# Front_LDR.net
KiCad netlist of a schematic drawn in Altium Designer
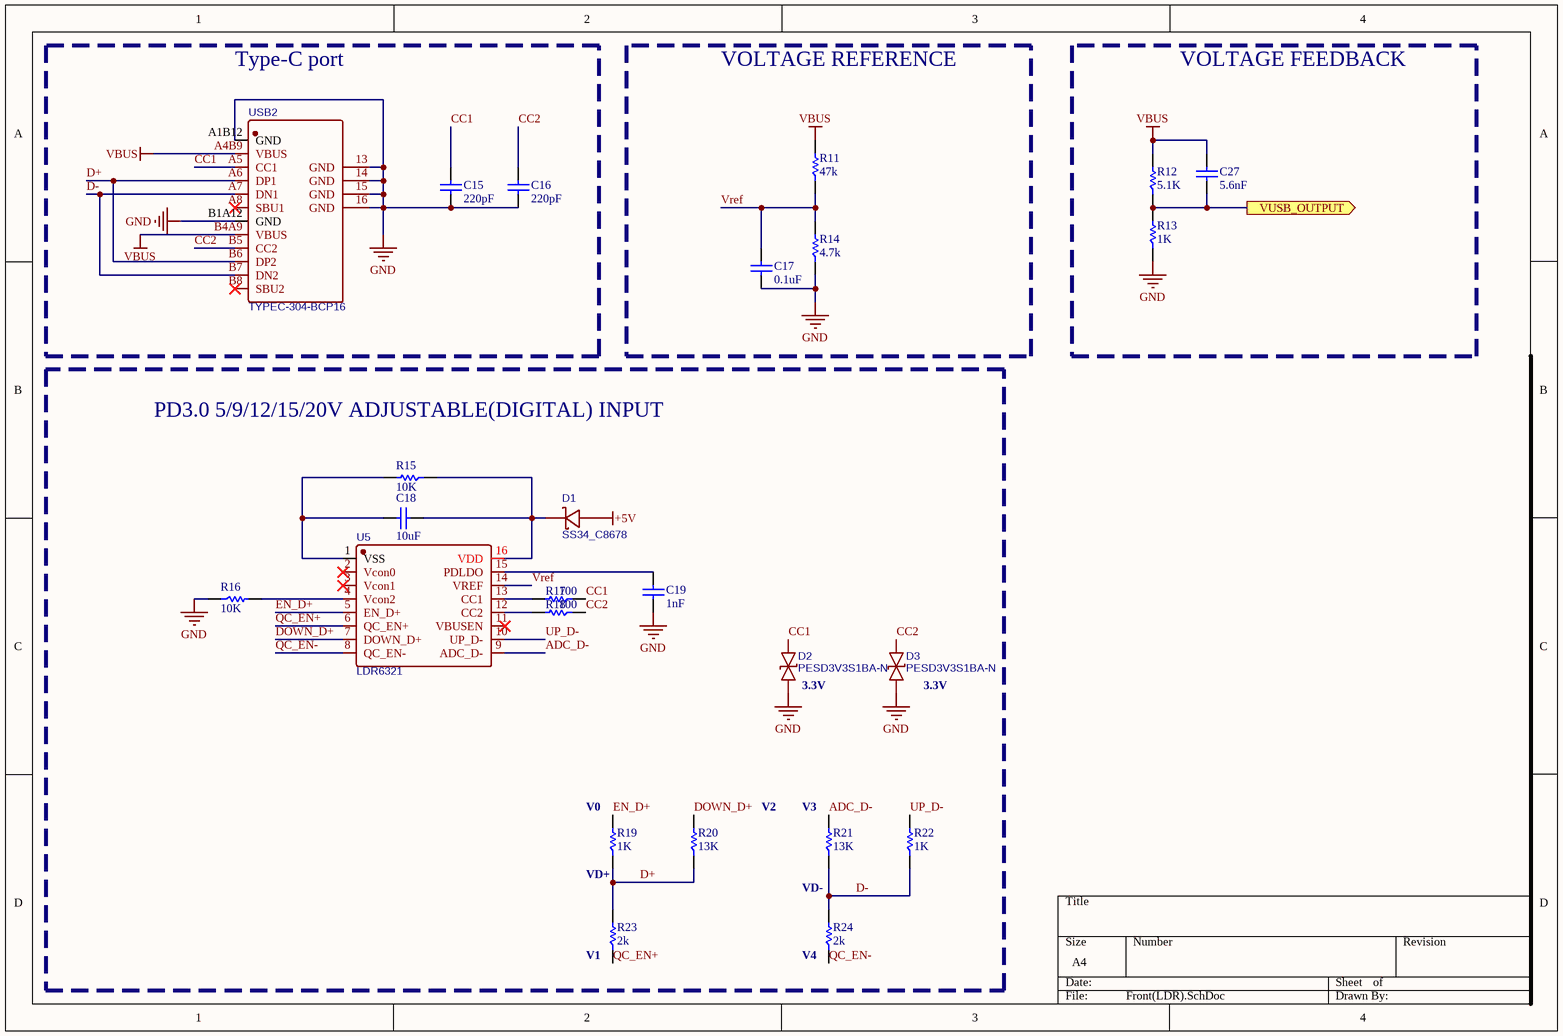
[diagram p0: Front(LDR).SchDoc]

(export (version "E")
  (design (tool "Eeschema 10.0.6"))
  (components
    (comp (ref "C15")
      (value "220pF")
      (footprint "0805C")
      (description "Capacitor")
      (fields (field (name "REVIEWED BY") "RM - 2018/08/05"))
      (libsource (lib "Portable power supply") (part "C_220pF"))
    )
    (comp (ref "C16")
      (value "220pF")
      (footprint "0805C")
      (description "Capacitor")
      (fields (field (name "REVIEWED BY") "RM - 2018/08/05"))
      (libsource (lib "Portable power supply") (part "C_220pF"))
    )
    (comp (ref "C17")
      (value "0.1uF")
      (footprint "0805C")
      (description "Capacitor")
      (fields (field (name "REVIEWED BY") "RM - 2018/08/05"))
      (libsource (lib "Portable power supply") (part "C_0.1uf"))
    )
    (comp (ref "C18")
      (value "10uF")
      (footprint "0805C")
      (description "Capacitor")
      (fields (field (name "REVIEWED BY") "RM - 2018/08/05"))
      (libsource (lib "Portable power supply") (part "C_10uf"))
    )
    (comp (ref "C19")
      (value "1nF")
      (footprint "0805C")
      (description "Capacitor")
      (fields (field (name "REVIEWED BY") "RM - 2018/08/05"))
      (libsource (lib "Portable power supply") (part "C_1nf"))
    )
    (comp (ref "C27")
      (value "5.6nF")
      (footprint "0805C")
      (description "Capacitor")
      (fields (field (name "REVIEWED BY") "RM - 2018/08/05"))
      (libsource (lib "Portable power supply") (part "C_5.6nf"))
    )
    (comp (ref "D1")
      (value "SS34_C8678")
      (footprint "DO-214AC_L4.3-W2.7-LS5.3-RD")
      (fields (field (name "BOM_MANUFACTURER PART") "SS34") (field (name "BOM_SUPPLIER PART") "C8678"))
      (libsource (lib "Portable power supply") (part "SS34_C8678"))
    )
    (comp (ref "D2")
      (value "PESD3V3S1BA-N")
      (footprint "SOD-523_L1.2-W0.8-LS1.6-BI")
      (description "TVS3V3")
      (fields (field (name "BOM_SUPPLIER PART") "C316037") (field (name "CONTRIBUTOR") "LCSC"))
      (libsource (lib "Portable power supply") (part "PESD3V3S1BA-N"))
    )
    (comp (ref "D3")
      (value "PESD3V3S1BA-N")
      (footprint "SOD-523_L1.2-W0.8-LS1.6-BI")
      (description "TVS3V3")
      (fields (field (name "BOM_SUPPLIER PART") "C316037") (field (name "CONTRIBUTOR") "LCSC"))
      (libsource (lib "Portable power supply") (part "PESD3V3S1BA-N"))
    )
    (comp (ref "R11")
      (value "47k")
      (footprint "0805")
      (description "Resistor")
      (fields (field (name "REVIEWED BY") "RM - 2018/08/05"))
      (libsource (lib "Portable power supply") (part "R_47k"))
    )
    (comp (ref "R12")
      (value "5.1K")
      (footprint "0805")
      (description "Resistor")
      (fields (field (name "REVIEWED BY") "RM - 2018/08/05"))
      (libsource (lib "Portable power supply") (part "R_5.1k"))
    )
    (comp (ref "R13")
      (value "1K")
      (footprint "0805")
      (description "Resistor")
      (fields (field (name "REVIEWED BY") "RM - 2018/08/05"))
      (libsource (lib "Portable power supply") (part "R_1k"))
    )
    (comp (ref "R14")
      (value "4.7k")
      (footprint "0805")
      (description "Resistor")
      (fields (field (name "REVIEWED BY") "RM - 2018/08/05"))
      (libsource (lib "Portable power supply") (part "R_4.7k"))
    )
    (comp (ref "R15")
      (value "10K")
      (footprint "0805")
      (description "Resistor")
      (fields (field (name "REVIEWED BY") "RM - 2018/08/05"))
      (libsource (lib "Portable power supply") (part "R_10k"))
    )
    (comp (ref "R16")
      (value "10K")
      (footprint "0805")
      (description "Resistor")
      (fields (field (name "REVIEWED BY") "RM - 2018/08/05"))
      (libsource (lib "Portable power supply") (part "R_10k"))
    )
    (comp (ref "R17")
      (value "100")
      (footprint "0805")
      (description "Resistor")
      (fields (field (name "REVIEWED BY") "RM - 2018/08/05"))
      (libsource (lib "Portable power supply") (part "R_100"))
    )
    (comp (ref "R18")
      (value "100")
      (footprint "0805")
      (description "Resistor")
      (fields (field (name "REVIEWED BY") "RM - 2018/08/05"))
      (libsource (lib "Portable power supply") (part "R_100"))
    )
    (comp (ref "R19")
      (value "1K")
      (footprint "0805")
      (description "Resistor")
      (fields (field (name "REVIEWED BY") "RM - 2018/08/05"))
      (libsource (lib "Portable power supply") (part "R_1k"))
    )
    (comp (ref "R20")
      (value "13K")
      (footprint "0805")
      (description "Resistor")
      (fields (field (name "REVIEWED BY") "RM - 2018/08/05"))
      (libsource (lib "Portable power supply") (part "R_13k"))
    )
    (comp (ref "R21")
      (value "13K")
      (footprint "0805")
      (description "Resistor")
      (fields (field (name "REVIEWED BY") "RM - 2018/08/05"))
      (libsource (lib "Portable power supply") (part "R_13k"))
    )
    (comp (ref "R22")
      (value "1K")
      (footprint "0805")
      (description "Resistor")
      (fields (field (name "REVIEWED BY") "RM - 2018/08/05"))
      (libsource (lib "Portable power supply") (part "R_1k"))
    )
    (comp (ref "R23")
      (value "2k")
      (footprint "0805")
      (description "Resistor")
      (fields (field (name "REVIEWED BY") "RM - 2018/08/05"))
      (libsource (lib "Portable power supply") (part "R_2k"))
    )
    (comp (ref "R24")
      (value "2k")
      (footprint "0805")
      (description "Resistor")
      (fields (field (name "REVIEWED BY") "RM - 2018/08/05"))
      (libsource (lib "Portable power supply") (part "R_2k"))
    )
    (comp (ref "U5")
      (value "LDR6321")
      (footprint "SSOP-16_L5.0-W4.4-P0.65-LS6.4-BL")
      (fields (field (name "BOM_SUPPLIER PART") "C2919632") (field (name "CONTRIBUTOR") "LCSC"))
      (libsource (lib "Portable power supply") (part "LDR6321"))
    )
    (comp (ref "USB2")
      (value "TYPEC-304-BCP16")
      (footprint "USB-C-SMD_TYPEC-304-BCP16")
      (fields (field (name "BOM_SUPPLIER PART") "C720629") (field (name "CONTRIBUTOR") "LCSC"))
      (libsource (lib "Portable power supply") (part "TYPEC-304-BCP16"))
    )
  )
  (nets
    (net (code "1") (name "+5V") (class "Default")
      (node (ref "D1") (pin "2") (pinfunction "A_2") (pintype "passive"))
    )
    (net (code "2") (name "/ADC_D-") (class "Default")
      (node (ref "R21") (pin "2") (pintype "passive"))
      (node (ref "U5") (pin "9") (pinfunction "ADC_D-_9") (pintype "passive"))
    )
    (net (code "3") (name "/CC1") (class "Default")
      (node (ref "C15") (pin "1") (pinfunction "1_1") (pintype "passive"))
      (node (ref "D2") (pin "2") (pinfunction "2_2") (pintype "passive"))
      (node (ref "R17") (pin "1") (pintype "passive"))
      (node (ref "USB2") (pin "A5") (pinfunction "CC1_A5") (pintype "passive"))
    )
    (net (code "4") (name "/CC2") (class "Default")
      (node (ref "C16") (pin "1") (pinfunction "1_1") (pintype "passive"))
      (node (ref "D3") (pin "2") (pinfunction "2_2") (pintype "passive"))
      (node (ref "R18") (pin "1") (pintype "passive"))
      (node (ref "USB2") (pin "B5") (pinfunction "CC2_B5") (pintype "passive"))
    )
    (net (code "5") (name "/D+") (class "Default")
      (node (ref "R19") (pin "1") (pintype "passive"))
      (node (ref "R20") (pin "1") (pintype "passive"))
      (node (ref "R23") (pin "2") (pintype "passive"))
      (node (ref "USB2") (pin "A6") (pinfunction "DP1_A6") (pintype "passive"))
      (node (ref "USB2") (pin "B6") (pinfunction "DP2_B6") (pintype "passive"))
    )
    (net (code "6") (name "/D-") (class "Default")
      (node (ref "R21") (pin "1") (pintype "passive"))
      (node (ref "R22") (pin "1") (pintype "passive"))
      (node (ref "R24") (pin "2") (pintype "passive"))
      (node (ref "USB2") (pin "A7") (pinfunction "DN1_A7") (pintype "passive"))
      (node (ref "USB2") (pin "B7") (pinfunction "DN2_B7") (pintype "passive"))
    )
    (net (code "7") (name "/DOWN_D+") (class "Default")
      (node (ref "R20") (pin "2") (pintype "passive"))
      (node (ref "U5") (pin "7") (pinfunction "DOWN_D+_7") (pintype "passive"))
    )
    (net (code "8") (name "/EN_D+") (class "Default")
      (node (ref "R19") (pin "2") (pintype "passive"))
      (node (ref "U5") (pin "5") (pinfunction "EN_D+_5") (pintype "passive"))
    )
    (net (code "9") (name "/QC_EN+") (class "Default")
      (node (ref "R23") (pin "1") (pintype "passive"))
      (node (ref "U5") (pin "6") (pinfunction "QC_EN+_6") (pintype "passive"))
    )
    (net (code "10") (name "/QC_EN-") (class "Default")
      (node (ref "R24") (pin "1") (pintype "passive"))
      (node (ref "U5") (pin "8") (pinfunction "QC_EN-_8") (pintype "passive"))
    )
    (net (code "11") (name "/UP_D-") (class "Default")
      (node (ref "R22") (pin "2") (pintype "passive"))
      (node (ref "U5") (pin "10") (pinfunction "UP_D-_10") (pintype "passive"))
    )
    (net (code "12") (name "/VUSB_OUTPUT") (class "Default")
      (node (ref "C27") (pin "2") (pinfunction "2_2") (pintype "passive"))
      (node (ref "R12") (pin "1") (pintype "passive"))
      (node (ref "R13") (pin "2") (pintype "passive"))
    )
    (net (code "13") (name "/Vref") (class "Default")
      (node (ref "C17") (pin "1") (pinfunction "1_1") (pintype "passive"))
      (node (ref "R11") (pin "1") (pintype "passive"))
      (node (ref "R14") (pin "2") (pintype "passive"))
      (node (ref "U5") (pin "14") (pinfunction "VREF_14") (pintype "passive"))
    )
    (net (code "14") (name "GND") (class "Default")
      (node (ref "C15") (pin "2") (pinfunction "2_2") (pintype "passive"))
      (node (ref "C16") (pin "2") (pinfunction "2_2") (pintype "passive"))
      (node (ref "C17") (pin "2") (pinfunction "2_2") (pintype "passive"))
      (node (ref "C19") (pin "2") (pinfunction "2_2") (pintype "passive"))
      (node (ref "D2") (pin "1") (pinfunction "1_1") (pintype "passive"))
      (node (ref "D3") (pin "1") (pinfunction "1_1") (pintype "passive"))
      (node (ref "R13") (pin "1") (pintype "passive"))
      (node (ref "R14") (pin "1") (pintype "passive"))
      (node (ref "R16") (pin "1") (pintype "passive"))
      (node (ref "USB2") (pin "13") (pinfunction "GND_13") (pintype "passive"))
      (node (ref "USB2") (pin "14") (pinfunction "GND_14") (pintype "passive"))
      (node (ref "USB2") (pin "15") (pinfunction "GND_15") (pintype "passive"))
      (node (ref "USB2") (pin "16") (pinfunction "GND_16") (pintype "passive"))
      (node (ref "USB2") (pin "A1B12") (pinfunction "GND_A1B12") (pintype "passive"))
      (node (ref "USB2") (pin "B1A12") (pinfunction "GND_B1A12") (pintype "passive"))
    )
    (net (code "15") (name "Net-(D1-K)") (class "Default")
      (node (ref "C18") (pin "2") (pinfunction "2_2") (pintype "passive"))
      (node (ref "D1") (pin "1") (pinfunction "K_1") (pintype "passive"))
      (node (ref "R15") (pin "1") (pintype "passive"))
      (node (ref "U5") (pin "16") (pinfunction "VDD_16") (pintype "passive"))
    )
    (net (code "16") (name "Net-(U5-CC1)") (class "Default")
      (node (ref "R17") (pin "2") (pintype "passive"))
      (node (ref "U5") (pin "13") (pinfunction "CC1_13") (pintype "passive"))
    )
    (net (code "17") (name "Net-(U5-CC2)") (class "Default")
      (node (ref "R18") (pin "2") (pintype "passive"))
      (node (ref "U5") (pin "12") (pinfunction "CC2_12") (pintype "passive"))
    )
    (net (code "18") (name "Net-(U5-PDLDO)") (class "Default")
      (node (ref "C19") (pin "1") (pinfunction "1_1") (pintype "passive"))
      (node (ref "U5") (pin "15") (pinfunction "PDLDO_15") (pintype "passive"))
    )
    (net (code "19") (name "Net-(U5-VSS)") (class "Default")
      (node (ref "C18") (pin "1") (pinfunction "1_1") (pintype "passive"))
      (node (ref "R15") (pin "2") (pintype "passive"))
      (node (ref "U5") (pin "1") (pinfunction "VSS_1") (pintype "passive"))
    )
    (net (code "20") (name "Net-(U5-Vcon2)") (class "Default")
      (node (ref "R16") (pin "2") (pintype "passive"))
      (node (ref "U5") (pin "4") (pinfunction "Vcon2_4") (pintype "passive"))
    )
    (net (code "21") (name "VBUS") (class "Default")
      (node (ref "C27") (pin "1") (pinfunction "1_1") (pintype "passive"))
      (node (ref "R11") (pin "2") (pintype "passive"))
      (node (ref "R12") (pin "2") (pintype "passive"))
      (node (ref "USB2") (pin "A4B9") (pinfunction "VBUS_A4B9") (pintype "passive"))
      (node (ref "USB2") (pin "B4A9") (pinfunction "VBUS_B4A9") (pintype "passive"))
    )
    (net (code "22") (name "unconnected-(U5-VBUSEN-Pad11)") (class "Default")
      (node (ref "U5") (pin "11") (pinfunction "VBUSEN_11") (pintype "passive+no_connect"))
    )
    (net (code "23") (name "unconnected-(U5-Vcon0-Pad2)") (class "Default")
      (node (ref "U5") (pin "2") (pinfunction "Vcon0_2") (pintype "passive+no_connect"))
    )
    (net (code "24") (name "unconnected-(U5-Vcon1-Pad3)") (class "Default")
      (node (ref "U5") (pin "3") (pinfunction "Vcon1_3") (pintype "passive+no_connect"))
    )
    (net (code "25") (name "unconnected-(USB2-SBU1-PadA8)") (class "Default")
      (node (ref "USB2") (pin "A8") (pinfunction "SBU1_A8") (pintype "passive+no_connect"))
    )
    (net (code "26") (name "unconnected-(USB2-SBU2-PadB8)") (class "Default")
      (node (ref "USB2") (pin "B8") (pinfunction "SBU2_B8") (pintype "passive+no_connect"))
    )
  )
)
